# AFC1.net
KiCad netlist of a schematic drawn in Altium Designer
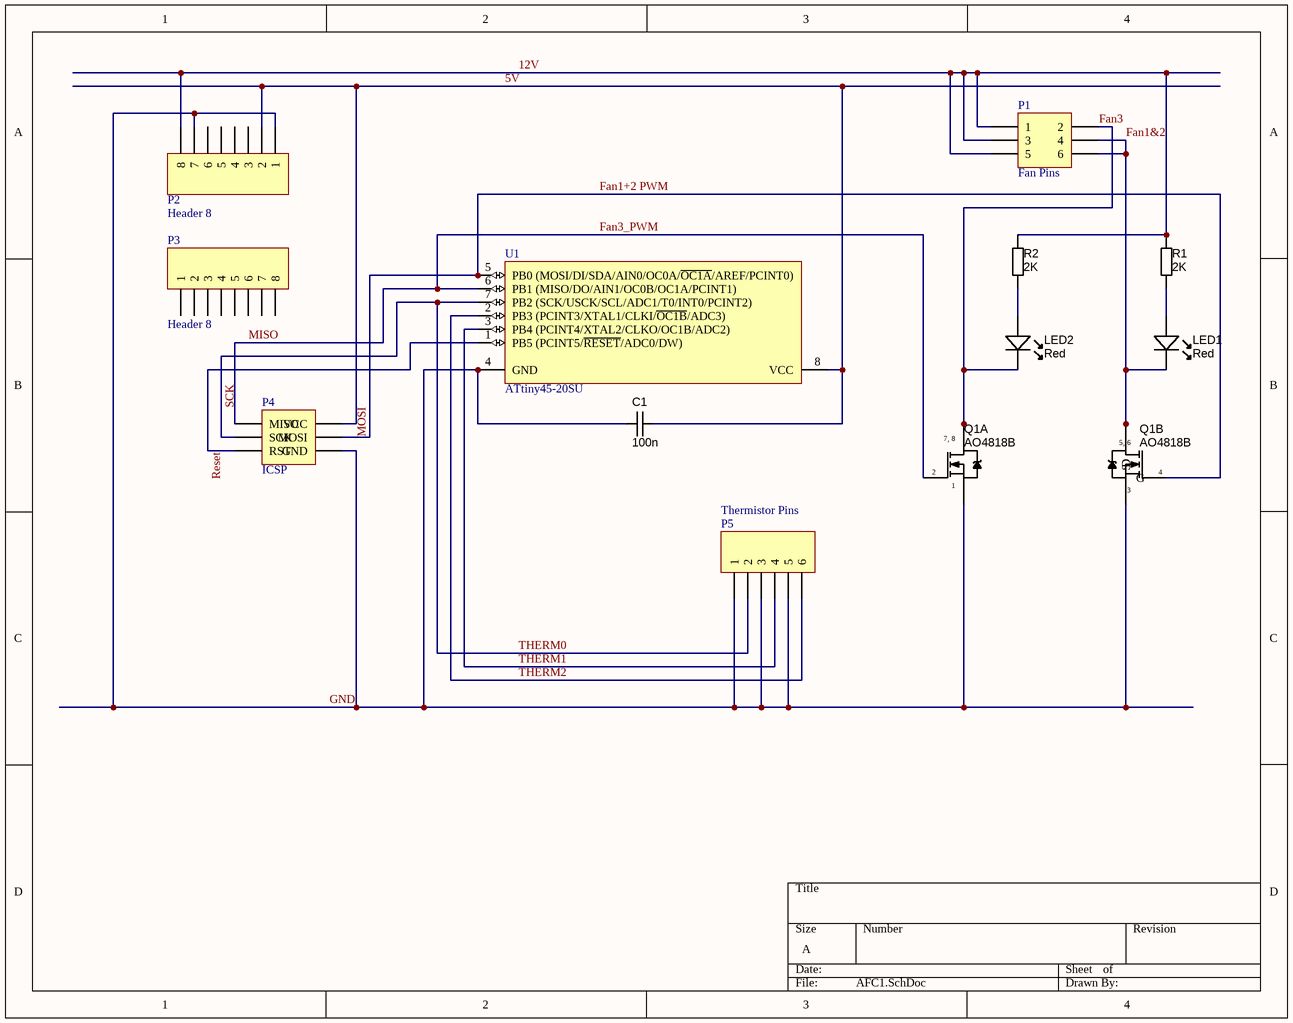
[diagram p0: AFC1.SchDoc]

(export (version "E")
  (design (tool "Eeschema 10.0.6"))
  (components
    (comp (ref "C1")
      (value "100n")
      (footprint "CAPC1005X55N")
      (description "Capacitor SMD Cer 100nF 10% 16V X5R 0402")
      (fields (field (name "TOLERANCE") "±10%"))
      (libsource (lib "PBL - Capacitors") (part "CAPC_100n_0402_X5R_16V_10%"))
    )
    (comp (ref "LED1")
      (value "Red")
      (footprint "LED-0603-RED")
      (description "LED 0603 SMD Hyper Red 630nm 220mcd 20mA")
      (libsource (lib "PBL - Light Sources") (part "LED_SMD_Red_0603_220mcd"))
    )
    (comp (ref "LED2")
      (value "Red")
      (footprint "LED-0603-RED")
      (description "LED 0603 SMD Hyper Red 630nm 220mcd 20mA")
      (libsource (lib "PBL - Light Sources") (part "LED_SMD_Red_0603_220mcd"))
    )
    (comp (ref "P1")
      (value "Fan Pins")
      (footprint "HDR2X3")
      (description "Header, 3-Pin, Dual row")
      (fields (field (name "PUBLISHER") "Altium Limited"))
      (libsource (lib "Miscellaneous Connectors") (part "Header 3X2"))
    )
    (comp (ref "P2")
      (value "Header 8")
      (footprint "HDR1X8")
      (description "Header, 8-Pin")
      (fields (field (name "PUBLISHER") "Altium Limited"))
      (libsource (lib "Miscellaneous Connectors") (part "Header 8"))
    )
    (comp (ref "P3")
      (value "Header 8")
      (footprint "HDR1X8")
      (description "Header, 8-Pin")
      (fields (field (name "PUBLISHER") "Altium Limited"))
      (libsource (lib "") (part "Header 8_1"))
    )
    (comp (ref "P4")
      (value "ICSP")
      (footprint "HDR2X3")
      (description "Header, 3-Pin, Dual row")
      (fields (field (name "PUBLISHER") "Altium Limited"))
      (libsource (lib "Miscellaneous Connectors") (part "Header 3X2"))
    )
    (comp (ref "P5")
      (value "Thermistor Pins")
      (footprint "HDR1X6")
      (description "Header, 6-Pin")
      (fields (field (name "PUBLISHER") "Altium Limited"))
      (libsource (lib "Miscellaneous Connectors") (part "Header 6"))
    )
    (comp (ref "Q1")
      (value "MOSFET_AO4818B")
      (footprint "SOIC127P600X175-8AN")
      (description "MOSFET Dual-Channel 30V 8.5A SOIC-8 SMD")
      (fields (field (name "MANUFACTURER PART NUMBER 1") "AO4818B"))
      (libsource (lib "") (part "MOSFET_AO4818B_1"))
    )
    (comp (ref "R1")
      (value "2K")
      (footprint "RESC1608X55N")
      (description "Resistor SMD chip 330 Ohm 0.1W 5% 0603")
      (fields (field (name "TOLERANCE") "±5%") (field (name "Comment") "Thick Film"))
      (libsource (lib "PBL - Resistors") (part "RES_330R_0603_5%"))
    )
    (comp (ref "R2")
      (value "2K")
      (footprint "RESC1608X55N")
      (description "Resistor SMD chip 330 Ohm 0.1W 5% 0603")
      (fields (field (name "TOLERANCE") "±5%") (field (name "Comment") "Thick Film"))
      (libsource (lib "PBL - Resistors") (part "RES_330R_0603_5%"))
    )
    (comp (ref "U1")
      (value "ATtiny45-20SU")
      (footprint "8S2_N")
      (libsource (lib "Atmel Microcontroller tinyAVR") (part "ATtiny45-20SU"))
    )
  )
  (nets
    (net (code "1") (name "/5V") (class "Default")
      (node (ref "C1") (pin "2") (pintype "passive"))
      (node (ref "P2") (pin "2") (pinfunction "2_2") (pintype "passive"))
      (node (ref "P4") (pin "2") (pinfunction "VCC_2") (pintype "passive"))
      (node (ref "U1") (pin "8") (pinfunction "VCC_8") (pintype "power_in"))
    )
    (net (code "2") (name "/12V") (class "Default")
      (node (ref "P1") (pin "1") (pinfunction "MISO_1") (pintype "passive"))
      (node (ref "P1") (pin "3") (pinfunction "SCK_3") (pintype "passive"))
      (node (ref "P1") (pin "5") (pinfunction "RST_5") (pintype "passive"))
      (node (ref "P2") (pin "8") (pinfunction "8_8") (pintype "passive"))
      (node (ref "R1") (pin "1") (pinfunction "1_1") (pintype "passive"))
      (node (ref "R2") (pin "1") (pinfunction "1_1") (pintype "passive"))
    )
    (net (code "3") (name "/Fan1&2") (class "Default")
      (node (ref "LED1") (pin "K") (pinfunction "K_K") (pintype "passive"))
      (node (ref "P1") (pin "4") (pinfunction "MOSI_4") (pintype "passive"))
      (node (ref "P1") (pin "6") (pinfunction "GND_6") (pintype "passive"))
      (node (ref "Q1") (pin "5") (pinfunction "D_5") (pintype "passive"))
      (node (ref "Q1") (pin "6") (pinfunction "D_6") (pintype "passive"))
    )
    (net (code "4") (name "/Fan1+2 PWM") (class "Default")
      (node (ref "P4") (pin "4") (pinfunction "MOSI_4") (pintype "passive"))
      (node (ref "Q1") (pin "4") (pinfunction "G_4") (pintype "passive"))
      (node (ref "U1") (pin "5") (pinfunction "PB0_(MOSI/DI/SDA/AIN0/OC0A/~{OC1A}/AREF/PCINT0)_5") (pintype "bidirectional"))
    )
    (net (code "5") (name "/Fan3") (class "Default")
      (node (ref "LED2") (pin "K") (pinfunction "K_K") (pintype "passive"))
      (node (ref "P1") (pin "2") (pinfunction "VCC_2") (pintype "passive"))
      (node (ref "Q1") (pin "7") (pinfunction "D_7") (pintype "passive"))
      (node (ref "Q1") (pin "8") (pinfunction "D_8") (pintype "passive"))
    )
    (net (code "6") (name "/Fan3_PWM") (class "Default")
      (node (ref "P4") (pin "1") (pinfunction "MISO_1") (pintype "passive"))
      (node (ref "Q1") (pin "2") (pinfunction "G_2") (pintype "passive"))
      (node (ref "U1") (pin "6") (pinfunction "PB1_(MISO/DO/AIN1/OC0B/OC1A/PCINT1)_6") (pintype "bidirectional"))
    )
    (net (code "7") (name "/GND") (class "Default")
      (node (ref "C1") (pin "1") (pintype "passive"))
      (node (ref "P2") (pin "1") (pinfunction "1_1") (pintype "passive"))
      (node (ref "P2") (pin "7") (pinfunction "7_7") (pintype "passive"))
      (node (ref "P4") (pin "6") (pinfunction "GND_6") (pintype "passive"))
      (node (ref "P5") (pin "1") (pinfunction "1_1") (pintype "passive"))
      (node (ref "P5") (pin "3") (pinfunction "3_3") (pintype "passive"))
      (node (ref "P5") (pin "5") (pinfunction "5_5") (pintype "passive"))
      (node (ref "Q1") (pin "1") (pinfunction "S_1") (pintype "passive"))
      (node (ref "Q1") (pin "3") (pinfunction "S_3") (pintype "passive"))
      (node (ref "U1") (pin "4") (pinfunction "GND_4") (pintype "power_in"))
    )
    (net (code "8") (name "/Reset") (class "Default")
      (node (ref "P4") (pin "5") (pinfunction "RST_5") (pintype "passive"))
      (node (ref "U1") (pin "1") (pinfunction "PB5_(PCINT5/~{RESET}/ADC0/DW)_1") (pintype "bidirectional"))
    )
    (net (code "9") (name "/SCK") (class "Default")
      (node (ref "P4") (pin "3") (pinfunction "SCK_3") (pintype "passive"))
      (node (ref "P5") (pin "2") (pinfunction "2_2") (pintype "passive"))
      (node (ref "U1") (pin "7") (pinfunction "PB2_(SCK/USCK/SCL/ADC1/T0/INT0/PCINT2)_7") (pintype "bidirectional"))
    )
    (net (code "10") (name "/THERM1") (class "Default")
      (node (ref "P5") (pin "4") (pinfunction "4_4") (pintype "passive"))
      (node (ref "U1") (pin "3") (pinfunction "PB4_(PCINT4/XTAL2/CLKO/OC1B/ADC2)_3") (pintype "bidirectional"))
    )
    (net (code "11") (name "/THERM2") (class "Default")
      (node (ref "P5") (pin "6") (pinfunction "6_6") (pintype "passive"))
      (node (ref "U1") (pin "2") (pinfunction "PB3_(PCINT3/XTAL1/CLKI/~{OC1B}/ADC3)_2") (pintype "bidirectional"))
    )
    (net (code "12") (name "Net-(LED1-PadA)") (class "Default")
      (node (ref "LED1") (pin "A") (pinfunction "A_A") (pintype "passive"))
      (node (ref "R1") (pin "2") (pinfunction "2_2") (pintype "passive"))
    )
    (net (code "13") (name "Net-(LED2-PadA)") (class "Default")
      (node (ref "LED2") (pin "A") (pinfunction "A_A") (pintype "passive"))
      (node (ref "R2") (pin "2") (pinfunction "2_2") (pintype "passive"))
    )
    (net (code "14") (name "unconnected-(P2-Pad3)") (class "Default")
      (node (ref "P2") (pin "3") (pinfunction "3_3") (pintype "passive"))
    )
    (net (code "15") (name "unconnected-(P2-Pad4)") (class "Default")
      (node (ref "P2") (pin "4") (pinfunction "4_4") (pintype "passive"))
    )
    (net (code "16") (name "unconnected-(P2-Pad5)") (class "Default")
      (node (ref "P2") (pin "5") (pinfunction "5_5") (pintype "passive"))
    )
    (net (code "17") (name "unconnected-(P2-Pad6)") (class "Default")
      (node (ref "P2") (pin "6") (pinfunction "6_6") (pintype "passive"))
    )
    (net (code "18") (name "unconnected-(P3-Pad1)") (class "Default")
      (node (ref "P3") (pin "1") (pinfunction "1_1") (pintype "passive"))
    )
    (net (code "19") (name "unconnected-(P3-Pad2)") (class "Default")
      (node (ref "P3") (pin "2") (pinfunction "2_2") (pintype "passive"))
    )
    (net (code "20") (name "unconnected-(P3-Pad3)") (class "Default")
      (node (ref "P3") (pin "3") (pinfunction "3_3") (pintype "passive"))
    )
    (net (code "21") (name "unconnected-(P3-Pad4)") (class "Default")
      (node (ref "P3") (pin "4") (pinfunction "4_4") (pintype "passive"))
    )
    (net (code "22") (name "unconnected-(P3-Pad5)") (class "Default")
      (node (ref "P3") (pin "5") (pinfunction "5_5") (pintype "passive"))
    )
    (net (code "23") (name "unconnected-(P3-Pad6)") (class "Default")
      (node (ref "P3") (pin "6") (pinfunction "6_6") (pintype "passive"))
    )
    (net (code "24") (name "unconnected-(P3-Pad7)") (class "Default")
      (node (ref "P3") (pin "7") (pinfunction "7_7") (pintype "passive"))
    )
    (net (code "25") (name "unconnected-(P3-Pad8)") (class "Default")
      (node (ref "P3") (pin "8") (pinfunction "8_8") (pintype "passive"))
    )
  )
)
